# BudgetCANv2_0.net
KiCad netlist of a schematic drawn in EAGLE
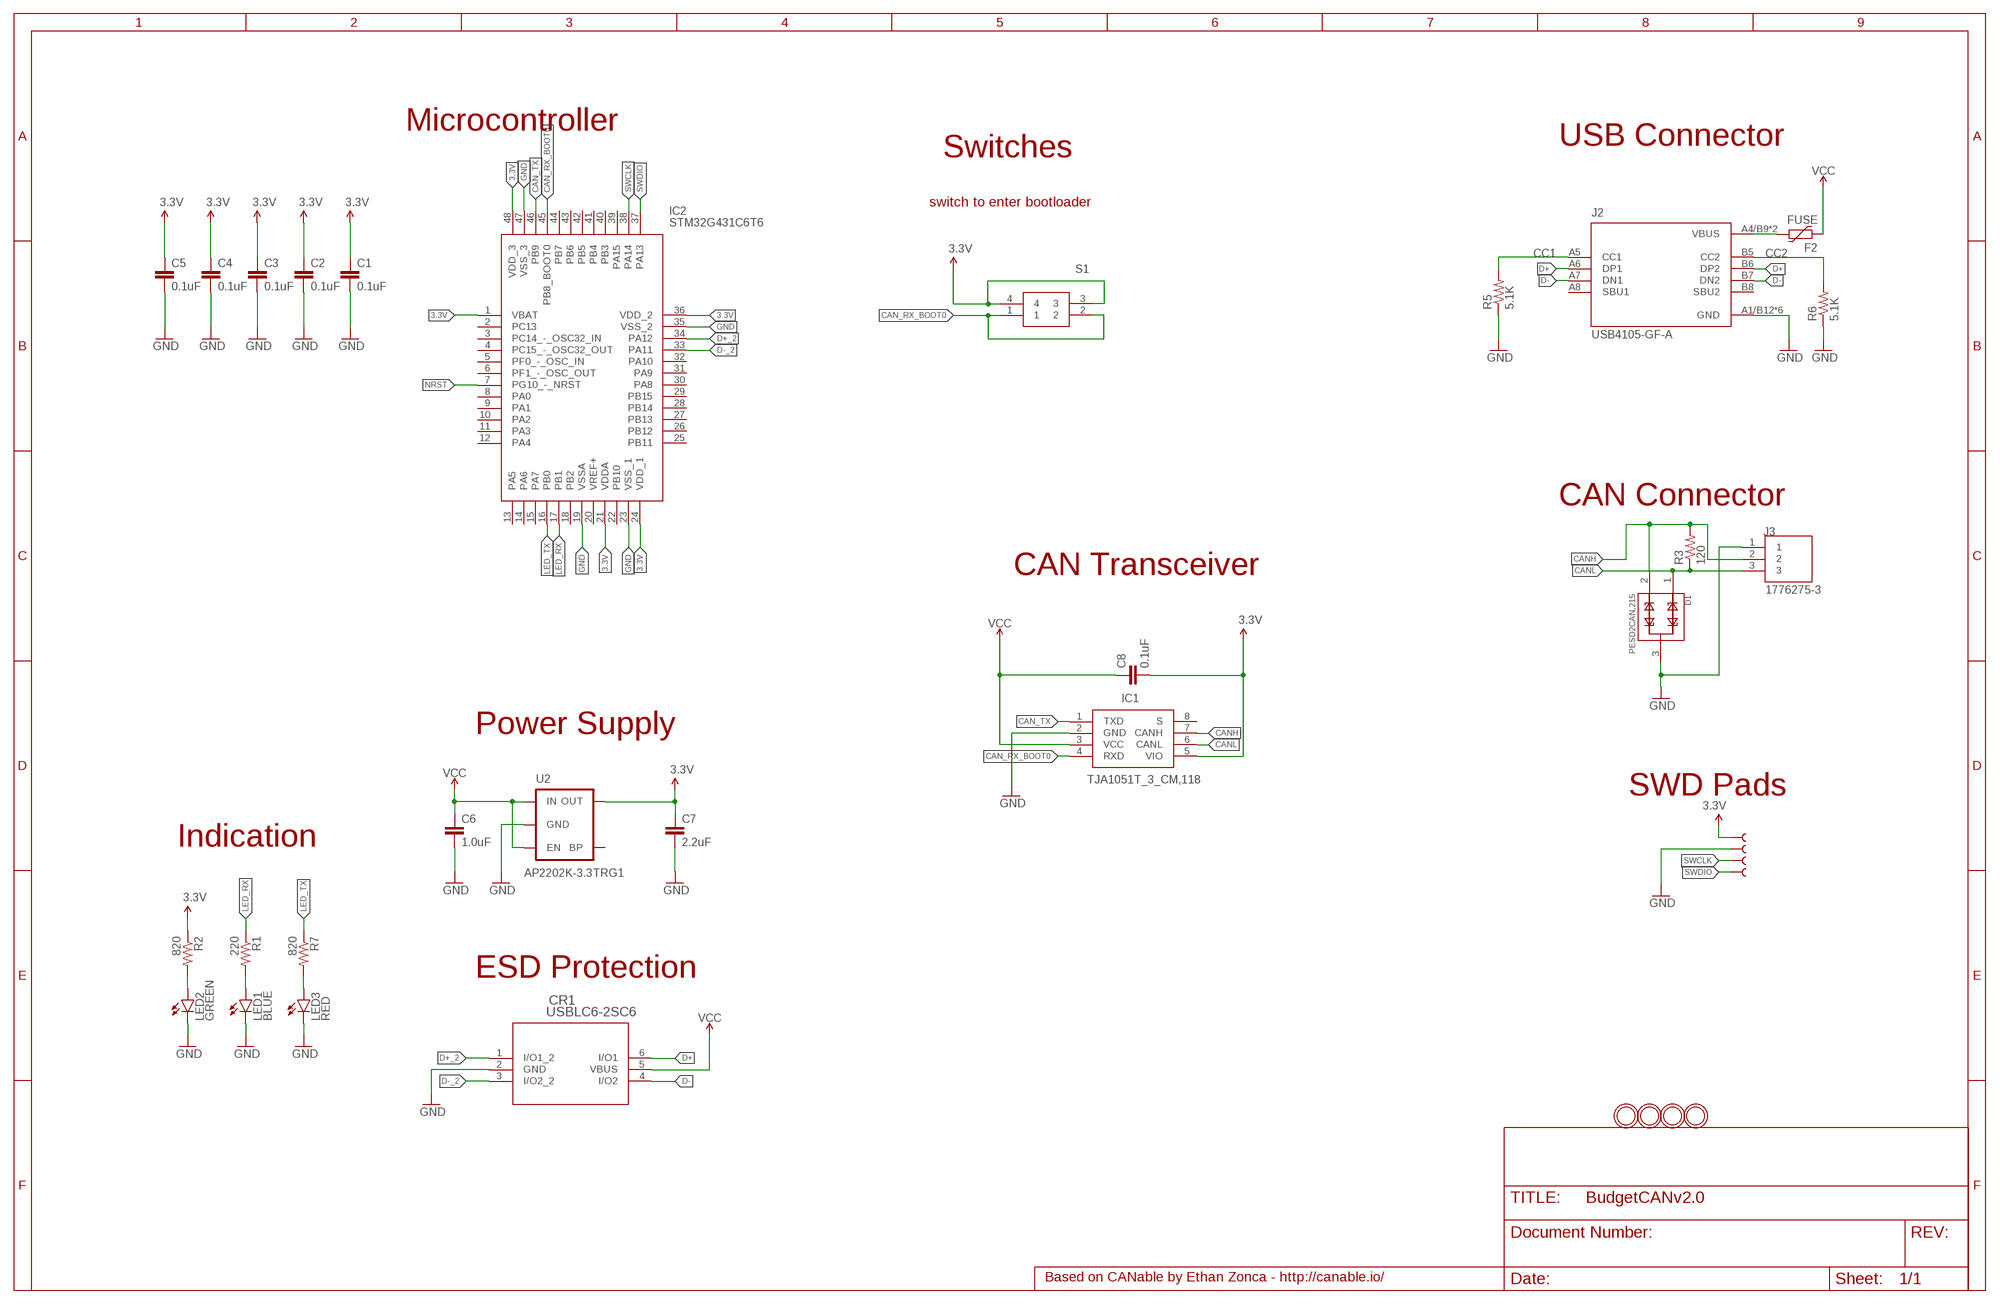
[diagram p0: schematic, sheet 1]

(export (version "E")
  (design (tool "Eeschema 10.0.6"))
  (components
    (comp (ref "C1")
      (value "0.1uF")
      (footprint "eagle-import:0603-CAP")
      (libsource (lib "eagle-import") (part "CAP0603-CAP"))
    )
    (comp (ref "C2")
      (value "0.1uF")
      (footprint "eagle-import:0603-CAP")
      (libsource (lib "eagle-import") (part "CAP0603-CAP"))
    )
    (comp (ref "C3")
      (value "0.1uF")
      (footprint "eagle-import:0603-CAP")
      (libsource (lib "eagle-import") (part "CAP0603-CAP"))
    )
    (comp (ref "C4")
      (value "0.1uF")
      (footprint "eagle-import:0603-CAP")
      (libsource (lib "eagle-import") (part "CAP0603-CAP"))
    )
    (comp (ref "C5")
      (value "0.1uF")
      (footprint "eagle-import:0603-CAP")
      (libsource (lib "eagle-import") (part "CAP0603-CAP"))
    )
    (comp (ref "C6")
      (value "1.0uF")
      (footprint "eagle-import:0603-CAP")
      (libsource (lib "eagle-import") (part "CAP0603-CAP"))
    )
    (comp (ref "C7")
      (value "2.2uF")
      (footprint "eagle-import:0603-CAP")
      (libsource (lib "eagle-import") (part "CAP0603-CAP"))
    )
    (comp (ref "C8")
      (value "0.1uF")
      (footprint "eagle-import:0603-CAP")
      (libsource (lib "eagle-import") (part "CAP0603-CAP"))
    )
    (comp (ref "CR1")
      (value "USBLC6-2SC6")
      (footprint "eagle-import:SOT23-6L")
      (libsource (lib "eagle-import") (part "USBLC6-2SC6"))
    )
    (comp (ref "D1")
      (value "PESD2CAN,215")
      (footprint "eagle-import:SOT95P230X110-3N")
      (fields (field (name "DIGI-KEY_PART_NUMBER") "1727-3891-1-ND") (field (name "MF") "Nexperia USA"))
      (libsource (lib "eagle-import") (part "PESD2CAN,215"))
    )
    (comp (ref "F2")
      (value "FUSE")
      (footprint "eagle-import:PTC0805")
      (libsource (lib "eagle-import") (part "FUSE_PTC-0805"))
    )
    (comp (ref "IC1")
      (value "TJA1051T_3_CM,118")
      (footprint "eagle-import:SOIC127P600X175-8N")
      (fields
        (field (name "MANUFACTURER_PART_NUMBER") "TJA1051T/3/CM,118")
        (field (name "MOUSER_PART_NUMBER") "771-TJA1051T/3CM118")
      )
      (libsource (lib "eagle-import") (part "TJA1051T_3_CM,118"))
    )
    (comp (ref "IC2")
      (value "STM32G431C6T6")
      (footprint "eagle-import:QFP50P900X900X160-48N")
      (fields (field (name "MOUSER_PART_NUMBER") "511-STM32G431C6T6"))
      (libsource (lib "eagle-import") (part "STM32G431C6T6"))
    )
    (comp (ref "J2")
      (value "USB4105-GF-A")
      (footprint "eagle-import:GCT_USB4105-GF-A")
      (fields (field (name "DIGI-KEY_PART_NUMBER") "2073-USB4105-GF-ACT-ND") (field (name "MF") "GCT"))
      (libsource (lib "eagle-import") (part "USB4105-GF-A"))
    )
    (comp (ref "J3")
      (value "1776275-3")
      (footprint "eagle-import:TE_1776275-3")
      (fields (field (name "MF") "TE Connectivity"))
      (libsource (lib "eagle-import") (part "1776275-3"))
    )
    (comp (ref "LED1")
      (value "BLUE")
      (footprint "eagle-import:LED-0603")
      (libsource (lib "eagle-import") (part "LED0603"))
    )
    (comp (ref "LED2")
      (value "GREEN")
      (footprint "eagle-import:LED-0603")
      (libsource (lib "eagle-import") (part "LED0603"))
    )
    (comp (ref "LED3")
      (value "RED")
      (footprint "eagle-import:LED-0603")
      (libsource (lib "eagle-import") (part "LED0603"))
    )
    (comp (ref "R1")
      (value "220")
      (footprint "eagle-import:0603-RES")
      (libsource (lib "eagle-import") (part "RESISTOR0603-RES"))
    )
    (comp (ref "R2")
      (value "820")
      (footprint "eagle-import:0603-RES")
      (libsource (lib "eagle-import") (part "RESISTOR0603-RES"))
    )
    (comp (ref "R3")
      (value "120")
      (footprint "eagle-import:0603-RES")
      (libsource (lib "eagle-import") (part "RESISTOR0603-RES"))
    )
    (comp (ref "R5")
      (value "5.1K")
      (footprint "eagle-import:0603-RES")
      (libsource (lib "eagle-import") (part "RESISTOR0603-RES"))
    )
    (comp (ref "R6")
      (value "5.1K")
      (footprint "eagle-import:0603-RES")
      (libsource (lib "eagle-import") (part "RESISTOR0603-RES"))
    )
    (comp (ref "R7")
      (value "820")
      (footprint "eagle-import:0603-RES")
      (libsource (lib "eagle-import") (part "RESISTOR0603-RES"))
    )
    (comp (ref "S1")
      (value "KMR631NGULCLFS")
      (footprint "eagle-import:KMR621NG")
      (fields (field (name "MOUSER_PART_NUMBER") "611-KMR631NGULCLFS"))
      (libsource (lib "eagle-import") (part "KMR631NGULCLFS"))
    )
    (comp (ref "TP1")
      (value "TEST-POINT3X5")
      (footprint "eagle-import:PAD.03X.05")
      (libsource (lib "eagle-import") (part "TEST-POINT3X5"))
    )
    (comp (ref "TP2")
      (value "TEST-POINT3X5")
      (footprint "eagle-import:PAD.03X.05")
      (libsource (lib "eagle-import") (part "TEST-POINT3X5"))
    )
    (comp (ref "TP3")
      (value "TEST-POINT3X5")
      (footprint "eagle-import:PAD.03X.05")
      (libsource (lib "eagle-import") (part "TEST-POINT3X5"))
    )
    (comp (ref "TP4")
      (value "TEST-POINT3X5")
      (footprint "eagle-import:PAD.03X.05")
      (libsource (lib "eagle-import") (part "TEST-POINT3X5"))
    )
    (comp (ref "U$2")
      (value "MOUNTINGHOLE3.0THIN")
      (footprint "eagle-import:MOUNTINGHOLE_3.0_PLATEDTHIN")
      (libsource (lib "eagle-import") (part "MOUNTINGHOLE3.0THIN"))
    )
    (comp (ref "U$3")
      (value "MOUNTINGHOLE3.0THIN")
      (footprint "eagle-import:MOUNTINGHOLE_3.0_PLATEDTHIN")
      (libsource (lib "eagle-import") (part "MOUNTINGHOLE3.0THIN"))
    )
    (comp (ref "U$4")
      (value "MOUNTINGHOLE3.0THIN")
      (footprint "eagle-import:MOUNTINGHOLE_3.0_PLATEDTHIN")
      (libsource (lib "eagle-import") (part "MOUNTINGHOLE3.0THIN"))
    )
    (comp (ref "U$5")
      (value "MOUNTINGHOLE3.0THIN")
      (footprint "eagle-import:MOUNTINGHOLE_3.0_PLATEDTHIN")
      (libsource (lib "eagle-import") (part "MOUNTINGHOLE3.0THIN"))
    )
    (comp (ref "U2")
      (value "AP2202K-3.3TRG1")
      (footprint "eagle-import:SOT23-5")
      (libsource (lib "eagle-import") (part "MIC52053.3V"))
    )
  )
  (nets
    (net (code "1") (name "/CC1") (class "Default")
      (node (ref "J2") (pin "A5") (pinfunction "CC1_A5") (pintype "bidirectional"))
      (node (ref "R5") (pin "2") (pinfunction "2_2") (pintype "passive"))
    )
    (net (code "2") (name "/CC2") (class "Default")
      (node (ref "J2") (pin "B5") (pinfunction "CC2_B5") (pintype "bidirectional"))
      (node (ref "R6") (pin "2") (pinfunction "2_2") (pintype "passive"))
    )
    (net (code "3") (name "3.3V") (class "Default")
      (node (ref "C1") (pin "1") (pinfunction "1_1") (pintype "passive"))
      (node (ref "C2") (pin "1") (pinfunction "1_1") (pintype "passive"))
      (node (ref "C3") (pin "1") (pinfunction "1_1") (pintype "passive"))
      (node (ref "C4") (pin "1") (pinfunction "1_1") (pintype "passive"))
      (node (ref "C5") (pin "1") (pinfunction "1_1") (pintype "passive"))
      (node (ref "C7") (pin "1") (pinfunction "1_1") (pintype "passive"))
      (node (ref "C8") (pin "2") (pinfunction "2_2") (pintype "passive"))
      (node (ref "IC1") (pin "5") (pinfunction "VIO_5") (pintype "bidirectional"))
      (node (ref "IC2") (pin "1") (pinfunction "VBAT_1") (pintype "bidirectional"))
      (node (ref "IC2") (pin "21") (pinfunction "VDDA_21") (pintype "bidirectional"))
      (node (ref "IC2") (pin "24") (pinfunction "VDD_1_24") (pintype "bidirectional"))
      (node (ref "IC2") (pin "36") (pinfunction "VDD_2_36") (pintype "bidirectional"))
      (node (ref "IC2") (pin "48") (pinfunction "VDD_3_48") (pintype "bidirectional"))
      (node (ref "R2") (pin "1") (pinfunction "1_1") (pintype "passive"))
      (node (ref "S1") (pin "3") (pinfunction "3_3") (pintype "bidirectional"))
      (node (ref "S1") (pin "4") (pinfunction "4_4") (pintype "bidirectional"))
      (node (ref "TP1") (pin "P$1") (pinfunction "1_P$1") (pintype "bidirectional"))
      (node (ref "U2") (pin "5") (pinfunction "OUT_5") (pintype "passive"))
    )
    (net (code "4") (name "CANH") (class "Default")
      (node (ref "D1") (pin "2") (pinfunction "2_2") (pintype "passive"))
      (node (ref "IC1") (pin "7") (pinfunction "CANH_7") (pintype "bidirectional"))
      (node (ref "J3") (pin "2") (pinfunction "2_2") (pintype "passive"))
      (node (ref "R3") (pin "2") (pinfunction "2_2") (pintype "passive"))
    )
    (net (code "5") (name "CANL") (class "Default")
      (node (ref "D1") (pin "1") (pinfunction "1_1") (pintype "passive"))
      (node (ref "IC1") (pin "6") (pinfunction "CANL_6") (pintype "bidirectional"))
      (node (ref "J3") (pin "3") (pinfunction "3_3") (pintype "passive"))
      (node (ref "R3") (pin "1") (pinfunction "1_1") (pintype "passive"))
    )
    (net (code "6") (name "CAN_RX_BOOT0") (class "Default")
      (node (ref "IC1") (pin "4") (pinfunction "RXD_4") (pintype "bidirectional"))
      (node (ref "IC2") (pin "45") (pinfunction "PB8_BOOT0_45") (pintype "bidirectional"))
      (node (ref "S1") (pin "1") (pinfunction "1_1") (pintype "bidirectional"))
      (node (ref "S1") (pin "2") (pinfunction "2_2") (pintype "bidirectional"))
    )
    (net (code "7") (name "CAN_TX") (class "Default")
      (node (ref "IC1") (pin "1") (pinfunction "TXD_1") (pintype "bidirectional"))
      (node (ref "IC2") (pin "46") (pinfunction "PB9_46") (pintype "bidirectional"))
    )
    (net (code "8") (name "D+") (class "Default")
      (node (ref "CR1") (pin "6") (pinfunction "I/O1_6") (pintype "bidirectional"))
      (node (ref "J2") (pin "A6") (pinfunction "DP1_A6") (pintype "bidirectional"))
      (node (ref "J2") (pin "B6") (pinfunction "DP2_B6") (pintype "bidirectional"))
    )
    (net (code "9") (name "D+_2") (class "Default")
      (node (ref "CR1") (pin "1") (pinfunction "I/O1_2_1") (pintype "bidirectional"))
      (node (ref "IC2") (pin "34") (pinfunction "PA12_34") (pintype "bidirectional"))
    )
    (net (code "10") (name "D-") (class "Default")
      (node (ref "CR1") (pin "4") (pinfunction "I/O2_4") (pintype "bidirectional"))
      (node (ref "J2") (pin "A7") (pinfunction "DN1_A7") (pintype "bidirectional"))
      (node (ref "J2") (pin "B7") (pinfunction "DN2_B7") (pintype "bidirectional"))
    )
    (net (code "11") (name "D-_2") (class "Default")
      (node (ref "CR1") (pin "3") (pinfunction "I/O2_2_3") (pintype "bidirectional"))
      (node (ref "IC2") (pin "33") (pinfunction "PA11_33") (pintype "bidirectional"))
    )
    (net (code "12") (name "GND") (class "Default")
      (node (ref "C1") (pin "2") (pinfunction "2_2") (pintype "passive"))
      (node (ref "C2") (pin "2") (pinfunction "2_2") (pintype "passive"))
      (node (ref "C3") (pin "2") (pinfunction "2_2") (pintype "passive"))
      (node (ref "C4") (pin "2") (pinfunction "2_2") (pintype "passive"))
      (node (ref "C5") (pin "2") (pinfunction "2_2") (pintype "passive"))
      (node (ref "C6") (pin "2") (pinfunction "2_2") (pintype "passive"))
      (node (ref "C7") (pin "2") (pinfunction "2_2") (pintype "passive"))
      (node (ref "CR1") (pin "2") (pinfunction "GND_2") (pintype "power_in"))
      (node (ref "D1") (pin "3") (pinfunction "3_3") (pintype "passive"))
      (node (ref "IC1") (pin "2") (pinfunction "GND_2") (pintype "power_in"))
      (node (ref "IC2") (pin "19") (pinfunction "VSSA_19") (pintype "bidirectional"))
      (node (ref "IC2") (pin "23") (pinfunction "VSS_1_23") (pintype "bidirectional"))
      (node (ref "IC2") (pin "35") (pinfunction "VSS_2_35") (pintype "bidirectional"))
      (node (ref "IC2") (pin "47") (pinfunction "VSS_3_47") (pintype "bidirectional"))
      (node (ref "J2") (pin "A1/B12") (pinfunction "GND_A1/B12") (pintype "power_in"))
      (node (ref "J2") (pin "B1/A12") (pinfunction "GND_B1/A12") (pintype "power_in"))
      (node (ref "J2") (pin "G1") (pinfunction "GND_G1") (pintype "power_in"))
      (node (ref "J2") (pin "G2") (pinfunction "GND_G2") (pintype "power_in"))
      (node (ref "J2") (pin "G3") (pinfunction "GND_G3") (pintype "power_in"))
      (node (ref "J2") (pin "G4") (pinfunction "GND_G4") (pintype "power_in"))
      (node (ref "J3") (pin "1") (pinfunction "1_1") (pintype "passive"))
      (node (ref "LED1") (pin "C") (pinfunction "C_C") (pintype "passive"))
      (node (ref "LED2") (pin "C") (pinfunction "C_C") (pintype "passive"))
      (node (ref "LED3") (pin "C") (pinfunction "C_C") (pintype "passive"))
      (node (ref "R5") (pin "1") (pinfunction "1_1") (pintype "passive"))
      (node (ref "R6") (pin "1") (pinfunction "1_1") (pintype "passive"))
      (node (ref "TP2") (pin "P$1") (pinfunction "1_P$1") (pintype "bidirectional"))
      (node (ref "U2") (pin "2") (pinfunction "GND_2") (pintype "input"))
    )
    (net (code "13") (name "LED_RX") (class "Default")
      (node (ref "IC2") (pin "17") (pinfunction "PB1_17") (pintype "bidirectional"))
      (node (ref "R1") (pin "1") (pinfunction "1_1") (pintype "passive"))
    )
    (net (code "14") (name "LED_TX") (class "Default")
      (node (ref "IC2") (pin "16") (pinfunction "PB0_16") (pintype "bidirectional"))
      (node (ref "R7") (pin "1") (pinfunction "1_1") (pintype "passive"))
    )
    (net (code "15") (name "NRST") (class "Default")
      (node (ref "IC2") (pin "7") (pinfunction "PG10_-_NRST_7") (pintype "bidirectional"))
    )
    (net (code "16") (name "Net-(F2-Pad2)") (class "Default")
      (node (ref "F2") (pin "2") (pinfunction "2_2") (pintype "passive"))
      (node (ref "J2") (pin "A4/B9") (pinfunction "VBUS_A4/B9") (pintype "power_in"))
      (node (ref "J2") (pin "B4/A9") (pinfunction "VBUS_B4/A9") (pintype "power_in"))
    )
    (net (code "17") (name "Net-(LED1-PadA)") (class "Default")
      (node (ref "LED1") (pin "A") (pinfunction "A_A") (pintype "passive"))
      (node (ref "R1") (pin "2") (pinfunction "2_2") (pintype "passive"))
    )
    (net (code "18") (name "Net-(LED2-PadA)") (class "Default")
      (node (ref "LED2") (pin "A") (pinfunction "A_A") (pintype "passive"))
      (node (ref "R2") (pin "2") (pinfunction "2_2") (pintype "passive"))
    )
    (net (code "19") (name "Net-(LED3-PadA)") (class "Default")
      (node (ref "LED3") (pin "A") (pinfunction "A_A") (pintype "passive"))
      (node (ref "R7") (pin "2") (pinfunction "2_2") (pintype "passive"))
    )
    (net (code "20") (name "SWCLK") (class "Default")
      (node (ref "IC2") (pin "38") (pinfunction "PA14_38") (pintype "bidirectional"))
      (node (ref "TP3") (pin "P$1") (pinfunction "1_P$1") (pintype "bidirectional"))
    )
    (net (code "21") (name "SWDIO") (class "Default")
      (node (ref "IC2") (pin "37") (pinfunction "PA13_37") (pintype "bidirectional"))
      (node (ref "TP4") (pin "P$1") (pinfunction "1_P$1") (pintype "bidirectional"))
    )
    (net (code "22") (name "VCC") (class "Default")
      (node (ref "C6") (pin "1") (pinfunction "1_1") (pintype "passive"))
      (node (ref "C8") (pin "1") (pinfunction "1_1") (pintype "passive"))
      (node (ref "CR1") (pin "5") (pinfunction "VBUS_5") (pintype "power_in"))
      (node (ref "F2") (pin "1") (pinfunction "1_1") (pintype "passive"))
      (node (ref "IC1") (pin "3") (pinfunction "VCC_3") (pintype "power_in"))
      (node (ref "U2") (pin "1") (pinfunction "IN_1") (pintype "input"))
      (node (ref "U2") (pin "3") (pinfunction "EN_3") (pintype "input"))
    )
    (net (code "23") (name "unconnected-(IC1-S-Pad8)") (class "Default")
      (node (ref "IC1") (pin "8") (pinfunction "S_8") (pintype "bidirectional"))
    )
    (net (code "24") (name "unconnected-(IC2-PA0-Pad8)") (class "Default")
      (node (ref "IC2") (pin "8") (pinfunction "PA0_8") (pintype "bidirectional"))
    )
    (net (code "25") (name "unconnected-(IC2-PA1-Pad9)") (class "Default")
      (node (ref "IC2") (pin "9") (pinfunction "PA1_9") (pintype "bidirectional"))
    )
    (net (code "26") (name "unconnected-(IC2-PA2-Pad10)") (class "Default")
      (node (ref "IC2") (pin "10") (pinfunction "PA2_10") (pintype "bidirectional"))
    )
    (net (code "27") (name "unconnected-(IC2-PA3-Pad11)") (class "Default")
      (node (ref "IC2") (pin "11") (pinfunction "PA3_11") (pintype "bidirectional"))
    )
    (net (code "28") (name "unconnected-(IC2-PA4-Pad12)") (class "Default")
      (node (ref "IC2") (pin "12") (pinfunction "PA4_12") (pintype "bidirectional"))
    )
    (net (code "29") (name "unconnected-(IC2-PA5-Pad13)") (class "Default")
      (node (ref "IC2") (pin "13") (pinfunction "PA5_13") (pintype "bidirectional"))
    )
    (net (code "30") (name "unconnected-(IC2-PA6-Pad14)") (class "Default")
      (node (ref "IC2") (pin "14") (pinfunction "PA6_14") (pintype "bidirectional"))
    )
    (net (code "31") (name "unconnected-(IC2-PA7-Pad15)") (class "Default")
      (node (ref "IC2") (pin "15") (pinfunction "PA7_15") (pintype "bidirectional"))
    )
    (net (code "32") (name "unconnected-(IC2-PA8-Pad30)") (class "Default")
      (node (ref "IC2") (pin "30") (pinfunction "PA8_30") (pintype "bidirectional"))
    )
    (net (code "33") (name "unconnected-(IC2-PA9-Pad31)") (class "Default")
      (node (ref "IC2") (pin "31") (pinfunction "PA9_31") (pintype "bidirectional"))
    )
    (net (code "34") (name "unconnected-(IC2-PA10-Pad32)") (class "Default")
      (node (ref "IC2") (pin "32") (pinfunction "PA10_32") (pintype "bidirectional"))
    )
    (net (code "35") (name "unconnected-(IC2-PA15-Pad39)") (class "Default")
      (node (ref "IC2") (pin "39") (pinfunction "PA15_39") (pintype "bidirectional"))
    )
    (net (code "36") (name "unconnected-(IC2-PB2-Pad18)") (class "Default")
      (node (ref "IC2") (pin "18") (pinfunction "PB2_18") (pintype "bidirectional"))
    )
    (net (code "37") (name "unconnected-(IC2-PB3-Pad40)") (class "Default")
      (node (ref "IC2") (pin "40") (pinfunction "PB3_40") (pintype "bidirectional"))
    )
    (net (code "38") (name "unconnected-(IC2-PB4-Pad41)") (class "Default")
      (node (ref "IC2") (pin "41") (pinfunction "PB4_41") (pintype "bidirectional"))
    )
    (net (code "39") (name "unconnected-(IC2-PB5-Pad42)") (class "Default")
      (node (ref "IC2") (pin "42") (pinfunction "PB5_42") (pintype "bidirectional"))
    )
    (net (code "40") (name "unconnected-(IC2-PB6-Pad43)") (class "Default")
      (node (ref "IC2") (pin "43") (pinfunction "PB6_43") (pintype "bidirectional"))
    )
    (net (code "41") (name "unconnected-(IC2-PB7-Pad44)") (class "Default")
      (node (ref "IC2") (pin "44") (pinfunction "PB7_44") (pintype "bidirectional"))
    )
    (net (code "42") (name "unconnected-(IC2-PB10-Pad22)") (class "Default")
      (node (ref "IC2") (pin "22") (pinfunction "PB10_22") (pintype "bidirectional"))
    )
    (net (code "43") (name "unconnected-(IC2-PB11-Pad25)") (class "Default")
      (node (ref "IC2") (pin "25") (pinfunction "PB11_25") (pintype "bidirectional"))
    )
    (net (code "44") (name "unconnected-(IC2-PB12-Pad26)") (class "Default")
      (node (ref "IC2") (pin "26") (pinfunction "PB12_26") (pintype "bidirectional"))
    )
    (net (code "45") (name "unconnected-(IC2-PB13-Pad27)") (class "Default")
      (node (ref "IC2") (pin "27") (pinfunction "PB13_27") (pintype "bidirectional"))
    )
    (net (code "46") (name "unconnected-(IC2-PB14-Pad28)") (class "Default")
      (node (ref "IC2") (pin "28") (pinfunction "PB14_28") (pintype "bidirectional"))
    )
    (net (code "47") (name "unconnected-(IC2-PB15-Pad29)") (class "Default")
      (node (ref "IC2") (pin "29") (pinfunction "PB15_29") (pintype "bidirectional"))
    )
    (net (code "48") (name "unconnected-(IC2-PC13-Pad2)") (class "Default")
      (node (ref "IC2") (pin "2") (pinfunction "PC13_2") (pintype "bidirectional"))
    )
    (net (code "49") (name "unconnected-(IC2-PC14_-_OSC32_IN-Pad3)") (class "Default")
      (node (ref "IC2") (pin "3") (pinfunction "PC14_-_OSC32_IN_3") (pintype "bidirectional"))
    )
    (net (code "50") (name "unconnected-(IC2-PC15_-_OSC32_OUT-Pad4)") (class "Default")
      (node (ref "IC2") (pin "4") (pinfunction "PC15_-_OSC32_OUT_4") (pintype "bidirectional"))
    )
    (net (code "51") (name "unconnected-(IC2-PF0_-_OSC_IN-Pad5)") (class "Default")
      (node (ref "IC2") (pin "5") (pinfunction "PF0_-_OSC_IN_5") (pintype "bidirectional"))
    )
    (net (code "52") (name "unconnected-(IC2-PF1_-_OSC_OUT-Pad6)") (class "Default")
      (node (ref "IC2") (pin "6") (pinfunction "PF1_-_OSC_OUT_6") (pintype "bidirectional"))
    )
    (net (code "53") (name "unconnected-(IC2-VREF+-Pad20)") (class "Default")
      (node (ref "IC2") (pin "20") (pinfunction "VREF+_20") (pintype "bidirectional"))
    )
    (net (code "54") (name "unconnected-(J2-SBU1-PadA8)") (class "Default")
      (node (ref "J2") (pin "A8") (pinfunction "SBU1_A8") (pintype "bidirectional"))
    )
    (net (code "55") (name "unconnected-(J2-SBU2-PadB8)") (class "Default")
      (node (ref "J2") (pin "B8") (pinfunction "SBU2_B8") (pintype "bidirectional"))
    )
    (net (code "56") (name "unconnected-(U2-BP-Pad4)") (class "Default")
      (node (ref "U2") (pin "4") (pinfunction "BP_4") (pintype "input"))
    )
  )
)
